# satshakit-mega.net
KiCad netlist of a schematic drawn in EAGLE
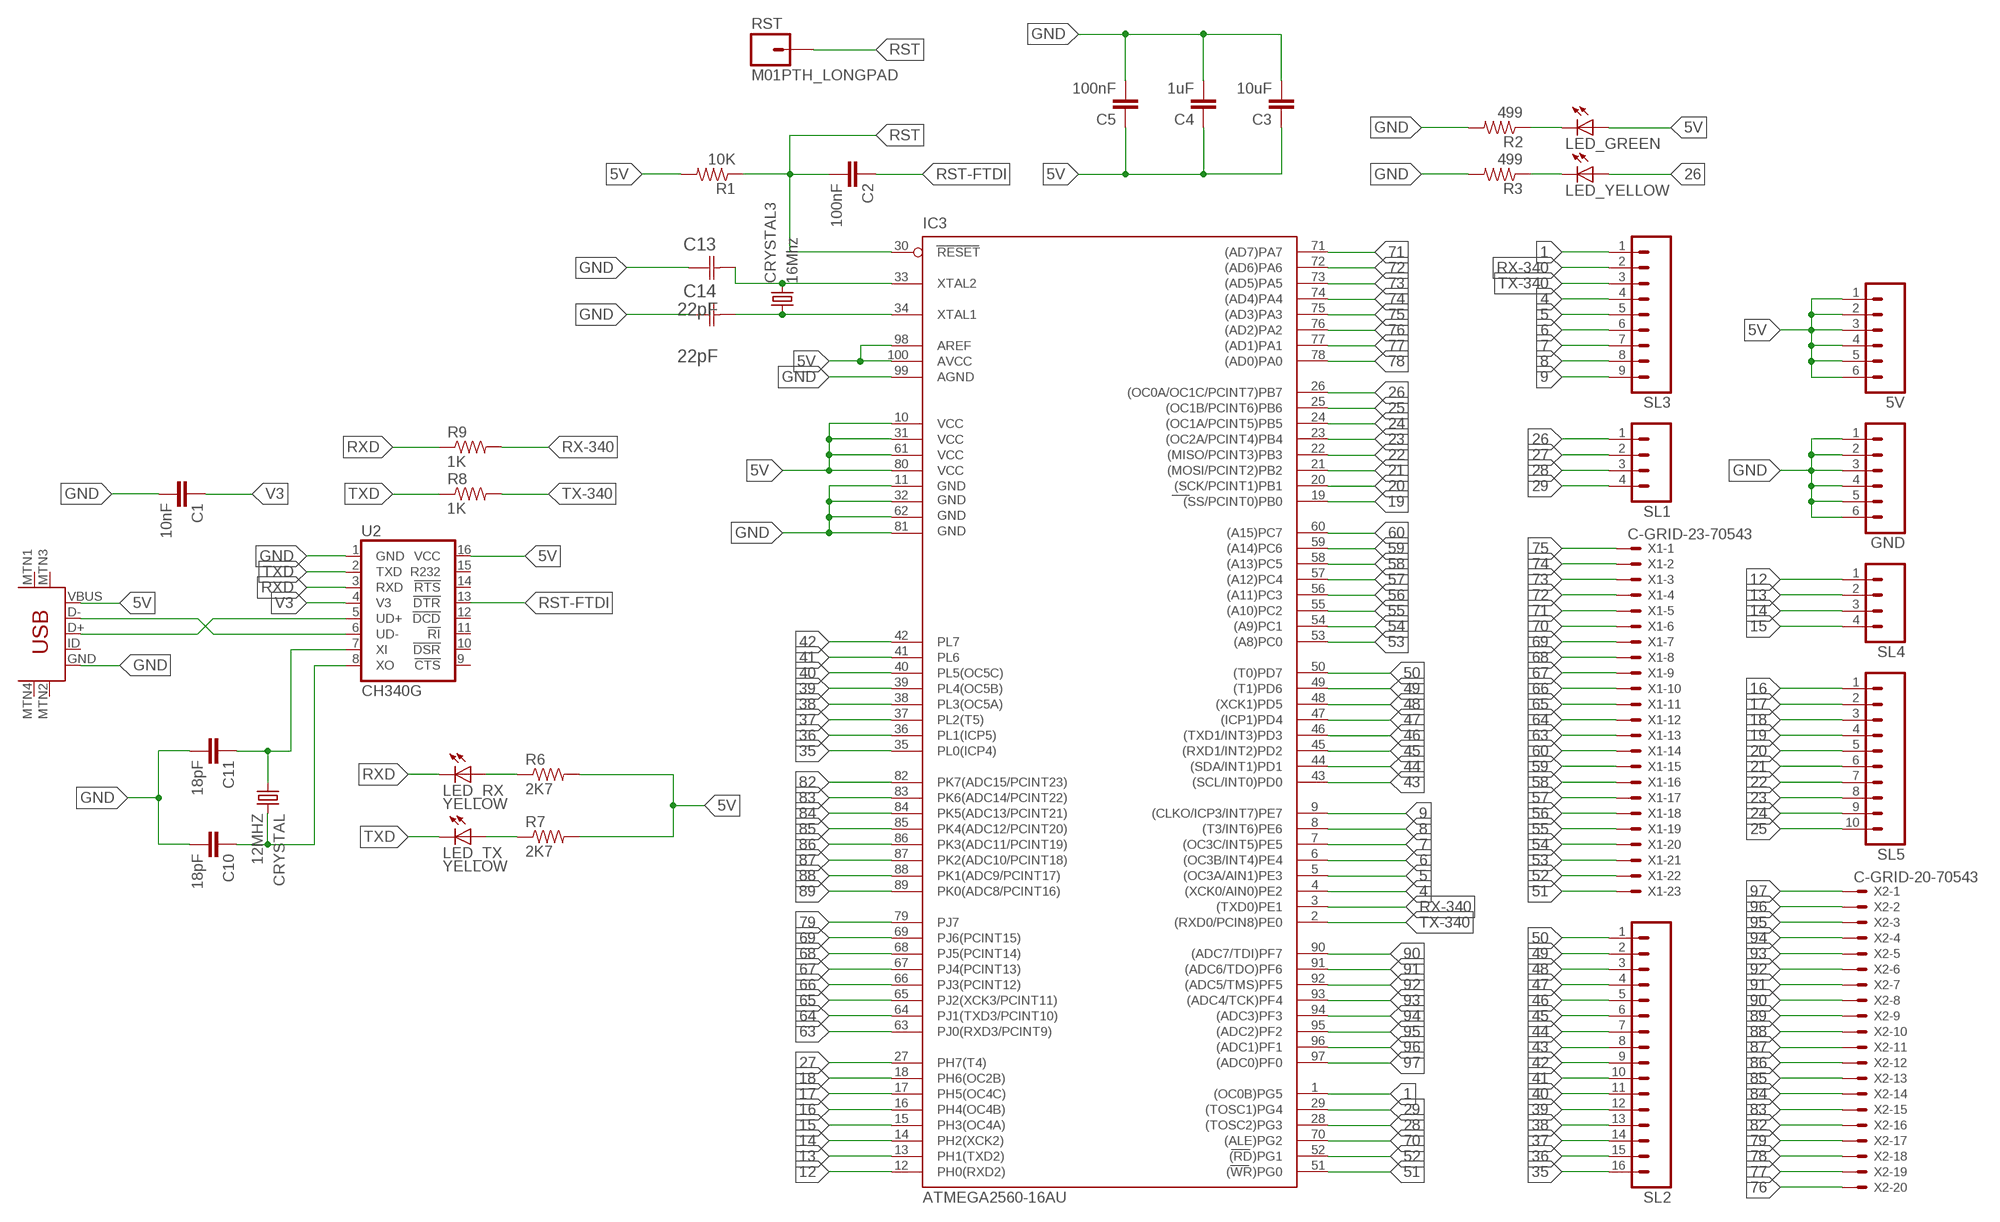
[diagram p0: schematic, sheet 1]

(export (version "E")
  (design (tool "Eeschema 10.0.6"))
  (components
    (comp (ref "5V")
      (value "M06")
      (footprint "eagle-import:06P")
      (libsource (lib "eagle-import") (part "M06"))
    )
    (comp (ref "C1")
      (value "10nF")
      (footprint "eagle-import:1206")
      (libsource (lib "eagle-import") (part "CAP1206"))
    )
    (comp (ref "C2")
      (value "100nF")
      (footprint "eagle-import:1206")
      (libsource (lib "eagle-import") (part "CAP1206"))
    )
    (comp (ref "C3")
      (value "10uF")
      (footprint "eagle-import:1206")
      (libsource (lib "eagle-import") (part "CAP1206"))
    )
    (comp (ref "C4")
      (value "1uF")
      (footprint "eagle-import:1206")
      (libsource (lib "eagle-import") (part "CAP1206"))
    )
    (comp (ref "C5")
      (value "100nF")
      (footprint "eagle-import:1206")
      (libsource (lib "eagle-import") (part "CAP1206"))
    )
    (comp (ref "C10")
      (value "18pF")
      (footprint "eagle-import:1206")
      (libsource (lib "eagle-import") (part "CAP1206"))
    )
    (comp (ref "C11")
      (value "18pF")
      (footprint "eagle-import:1206")
      (libsource (lib "eagle-import") (part "CAP1206"))
    )
    (comp (ref "C13")
      (value "22pF")
      (footprint "eagle-import:CAPC3216X178N")
      (fields (field (name "MPN") "0612ZC225MAT2A") (field (name "TOLERANCE") "±20%"))
      (libsource (lib "eagle-import") (part "0612ZC225MAT2A"))
    )
    (comp (ref "C14")
      (value "22pF")
      (footprint "eagle-import:CAPC3216X178N")
      (fields (field (name "MPN") "0612ZC225MAT2A") (field (name "TOLERANCE") "±20%"))
      (libsource (lib "eagle-import") (part "0612ZC225MAT2A"))
    )
    (comp (ref "CRYSTAL")
      (value "12MHZ")
      (footprint "eagle-import:CSM-7X-DU")
      (libsource (lib "eagle-import") (part "flight_controller.lbr01_FAB_Hello_CSM-7X-DU"))
    )
    (comp (ref "CRYSTAL3")
      (value "16Mhz")
      (footprint "eagle-import:CSM-7X-DU")
      (libsource (lib "eagle-import") (part "CSM-7X-DU"))
    )
    (comp (ref "GND")
      (value "M06")
      (footprint "eagle-import:06P")
      (libsource (lib "eagle-import") (part "M06"))
    )
    (comp (ref "IC3")
      (value "ATMEGA2560-16AU")
      (footprint "eagle-import:TQFP100")
      (libsource (lib "eagle-import") (part "ATMEGAAU1280-16"))
    )
    (comp (ref "LED_GREEN")
      (value "LED1206")
      (footprint "eagle-import:1206")
      (libsource (lib "eagle-import") (part "LED1206"))
    )
    (comp (ref "LED_RX")
      (value "YELLOW")
      (footprint "eagle-import:LED1206")
      (libsource (lib "eagle-import") (part "LED"))
    )
    (comp (ref "LED_TX")
      (value "YELLOW")
      (footprint "eagle-import:LED1206")
      (libsource (lib "eagle-import") (part "LED"))
    )
    (comp (ref "LED_YELLOW")
      (value "LED1206")
      (footprint "eagle-import:1206")
      (libsource (lib "eagle-import") (part "LED1206"))
    )
    (comp (ref "R1")
      (value "10K")
      (footprint "eagle-import:R1206")
      (libsource (lib "eagle-import") (part "RES-US1206"))
    )
    (comp (ref "R2")
      (value "499")
      (footprint "eagle-import:1206")
      (libsource (lib "eagle-import") (part "RESISTOR1206"))
    )
    (comp (ref "R3")
      (value "499")
      (footprint "eagle-import:1206")
      (libsource (lib "eagle-import") (part "RESISTOR1206"))
    )
    (comp (ref "R6")
      (value "2K7")
      (footprint "eagle-import:R1206")
      (libsource (lib "eagle-import") (part "RES-US1206"))
    )
    (comp (ref "R7")
      (value "2K7")
      (footprint "eagle-import:R1206")
      (libsource (lib "eagle-import") (part "RES-US1206"))
    )
    (comp (ref "R8")
      (value "1K")
      (footprint "eagle-import:R1206")
      (libsource (lib "eagle-import") (part "RES-US1206"))
    )
    (comp (ref "R9")
      (value "1K")
      (footprint "eagle-import:R1206")
      (libsource (lib "eagle-import") (part "RES-US1206"))
    )
    (comp (ref "RST")
      (value "M01PTH_LONGPAD")
      (footprint "eagle-import:1X01_LONGPAD")
      (libsource (lib "eagle-import") (part "M01PTH_LONGPAD"))
    )
    (comp (ref "SL1")
      (value "M04")
      (footprint "eagle-import:04P")
      (libsource (lib "eagle-import") (part "M04"))
    )
    (comp (ref "SL2")
      (value "M16")
      (footprint "eagle-import:16P")
      (libsource (lib "eagle-import") (part "M16"))
    )
    (comp (ref "SL3")
      (value "M09")
      (footprint "eagle-import:09P")
      (libsource (lib "eagle-import") (part "M09"))
    )
    (comp (ref "SL4")
      (value "M04")
      (footprint "eagle-import:04P")
      (libsource (lib "eagle-import") (part "M04"))
    )
    (comp (ref "SL5")
      (value "M10")
      (footprint "eagle-import:10P")
      (libsource (lib "eagle-import") (part "M10"))
    )
    (comp (ref "U$7")
      (value "USB-MINIB-5PIN")
      (footprint "eagle-import:USB-MINIB")
      (libsource (lib "eagle-import") (part "USB-MINIB-5PIN"))
    )
    (comp (ref "U2")
      (value "CH340G")
      (footprint "eagle-import:SO016")
      (libsource (lib "eagle-import") (part "CH340GSMD"))
    )
    (comp (ref "X1")
      (value "C-GRID-23-70543")
      (footprint "eagle-import:70543-23")
      (libsource (lib "eagle-import") (part "C-GRID-23-70543"))
    )
    (comp (ref "X2")
      (value "C-GRID-20-70543")
      (footprint "eagle-import:70543-20")
      (libsource (lib "eagle-import") (part "C-GRID-20-70543"))
    )
  )
  (nets
    (net (code "1") (name "1") (class "Default")
      (node (ref "IC3") (pin "1") (pinfunction "(OC0B)PG5_1") (pintype "bidirectional"))
      (node (ref "SL3") (pin "1") (pinfunction "1_1") (pintype "passive"))
    )
    (net (code "2") (name "4") (class "Default")
      (node (ref "IC3") (pin "4") (pinfunction "(XCK0/AIN0)PE2_4") (pintype "bidirectional"))
      (node (ref "SL3") (pin "4") (pinfunction "4_4") (pintype "passive"))
    )
    (net (code "3") (name "5") (class "Default")
      (node (ref "IC3") (pin "5") (pinfunction "(OC3A/AIN1)PE3_5") (pintype "bidirectional"))
      (node (ref "SL3") (pin "5") (pinfunction "5_5") (pintype "passive"))
    )
    (net (code "4") (name "5V") (class "Default")
      (node (ref "5V") (pin "1") (pinfunction "1_1") (pintype "passive"))
      (node (ref "5V") (pin "2") (pinfunction "2_2") (pintype "passive"))
      (node (ref "5V") (pin "3") (pinfunction "3_3") (pintype "passive"))
      (node (ref "5V") (pin "4") (pinfunction "4_4") (pintype "passive"))
      (node (ref "5V") (pin "5") (pinfunction "5_5") (pintype "passive"))
      (node (ref "5V") (pin "6") (pinfunction "6_6") (pintype "passive"))
      (node (ref "C3") (pin "1") (pinfunction "1_1") (pintype "passive"))
      (node (ref "C4") (pin "1") (pinfunction "1_1") (pintype "passive"))
      (node (ref "C5") (pin "1") (pinfunction "1_1") (pintype "passive"))
      (node (ref "IC3") (pin "10") (pinfunction "VCC_10") (pintype "power_in"))
      (node (ref "IC3") (pin "100") (pinfunction "AVCC_100") (pintype "power_in"))
      (node (ref "IC3") (pin "31") (pinfunction "VCC1_31") (pintype "power_in"))
      (node (ref "IC3") (pin "61") (pinfunction "VCC2_61") (pintype "power_in"))
      (node (ref "IC3") (pin "80") (pinfunction "VCC3_80") (pintype "power_in"))
      (node (ref "IC3") (pin "98") (pinfunction "AREF_98") (pintype "bidirectional"))
      (node (ref "LED_GREEN") (pin "1") (pinfunction "A_1") (pintype "passive"))
      (node (ref "R1") (pin "2") (pinfunction "2_2") (pintype "passive"))
      (node (ref "R6") (pin "2") (pinfunction "2_2") (pintype "passive"))
      (node (ref "R7") (pin "2") (pinfunction "2_2") (pintype "passive"))
      (node (ref "U$7") (pin "VBUS") (pinfunction "VBUS_VBUS") (pintype "bidirectional"))
      (node (ref "U2") (pin "16") (pinfunction "VCC_16") (pintype "bidirectional"))
    )
    (net (code "5") (name "6") (class "Default")
      (node (ref "IC3") (pin "6") (pinfunction "(OC3B/INT4)PE4_6") (pintype "bidirectional"))
      (node (ref "SL3") (pin "6") (pinfunction "6_6") (pintype "passive"))
    )
    (net (code "6") (name "7") (class "Default")
      (node (ref "IC3") (pin "7") (pinfunction "(OC3C/INT5)PE5_7") (pintype "bidirectional"))
      (node (ref "SL3") (pin "7") (pinfunction "7_7") (pintype "passive"))
    )
    (net (code "7") (name "8") (class "Default")
      (node (ref "IC3") (pin "8") (pinfunction "(T3/INT6)PE6_8") (pintype "bidirectional"))
      (node (ref "SL3") (pin "8") (pinfunction "8_8") (pintype "passive"))
    )
    (net (code "8") (name "9") (class "Default")
      (node (ref "IC3") (pin "9") (pinfunction "(CLKO/ICP3/INT7)PE7_9") (pintype "bidirectional"))
      (node (ref "SL3") (pin "9") (pinfunction "9_9") (pintype "passive"))
    )
    (net (code "9") (name "12") (class "Default")
      (node (ref "IC3") (pin "12") (pinfunction "PH0(RXD2)_12") (pintype "bidirectional"))
      (node (ref "SL4") (pin "1") (pinfunction "1_1") (pintype "passive"))
    )
    (net (code "10") (name "13") (class "Default")
      (node (ref "IC3") (pin "13") (pinfunction "PH1(TXD2)_13") (pintype "bidirectional"))
      (node (ref "SL4") (pin "2") (pinfunction "2_2") (pintype "passive"))
    )
    (net (code "11") (name "14") (class "Default")
      (node (ref "IC3") (pin "14") (pinfunction "PH2(XCK2)_14") (pintype "bidirectional"))
      (node (ref "SL4") (pin "3") (pinfunction "3_3") (pintype "passive"))
    )
    (net (code "12") (name "15") (class "Default")
      (node (ref "IC3") (pin "15") (pinfunction "PH3(OC4A)_15") (pintype "bidirectional"))
      (node (ref "SL4") (pin "4") (pinfunction "4_4") (pintype "passive"))
    )
    (net (code "13") (name "16") (class "Default")
      (node (ref "IC3") (pin "16") (pinfunction "PH4(OC4B)_16") (pintype "bidirectional"))
      (node (ref "SL5") (pin "1") (pinfunction "1_1") (pintype "passive"))
    )
    (net (code "14") (name "17") (class "Default")
      (node (ref "IC3") (pin "17") (pinfunction "PH5(OC4C)_17") (pintype "bidirectional"))
      (node (ref "SL5") (pin "2") (pinfunction "2_2") (pintype "passive"))
    )
    (net (code "15") (name "18") (class "Default")
      (node (ref "IC3") (pin "18") (pinfunction "PH6(OC2B)_18") (pintype "bidirectional"))
      (node (ref "SL5") (pin "3") (pinfunction "3_3") (pintype "passive"))
    )
    (net (code "16") (name "19") (class "Default")
      (node (ref "IC3") (pin "19") (pinfunction "(SS/PCINT0)PB0_19") (pintype "bidirectional"))
      (node (ref "SL5") (pin "4") (pinfunction "4_4") (pintype "passive"))
    )
    (net (code "17") (name "20") (class "Default")
      (node (ref "IC3") (pin "20") (pinfunction "(SCK/PCINT1)PB1_20") (pintype "bidirectional"))
      (node (ref "SL5") (pin "5") (pinfunction "5_5") (pintype "passive"))
    )
    (net (code "18") (name "21") (class "Default")
      (node (ref "IC3") (pin "21") (pinfunction "(MOSI/PCINT2)PB2_21") (pintype "bidirectional"))
      (node (ref "SL5") (pin "6") (pinfunction "6_6") (pintype "passive"))
    )
    (net (code "19") (name "22") (class "Default")
      (node (ref "IC3") (pin "22") (pinfunction "(MISO/PCINT3)PB3_22") (pintype "bidirectional"))
      (node (ref "SL5") (pin "7") (pinfunction "7_7") (pintype "passive"))
    )
    (net (code "20") (name "23") (class "Default")
      (node (ref "IC3") (pin "23") (pinfunction "(OC2A/PCINT4)PB4_23") (pintype "bidirectional"))
      (node (ref "SL5") (pin "8") (pinfunction "8_8") (pintype "passive"))
    )
    (net (code "21") (name "24") (class "Default")
      (node (ref "IC3") (pin "24") (pinfunction "(OC1A/PCINT5)PB5_24") (pintype "bidirectional"))
      (node (ref "SL5") (pin "9") (pinfunction "9_9") (pintype "passive"))
    )
    (net (code "22") (name "25") (class "Default")
      (node (ref "IC3") (pin "25") (pinfunction "(OC1B/PCINT6)PB6_25") (pintype "bidirectional"))
      (node (ref "SL5") (pin "10") (pinfunction "10_10") (pintype "passive"))
    )
    (net (code "23") (name "26") (class "Default")
      (node (ref "IC3") (pin "26") (pinfunction "(OC0A/OC1C/PCINT7)PB7_26") (pintype "bidirectional"))
      (node (ref "LED_YELLOW") (pin "1") (pinfunction "A_1") (pintype "passive"))
      (node (ref "SL1") (pin "1") (pinfunction "1_1") (pintype "passive"))
    )
    (net (code "24") (name "27") (class "Default")
      (node (ref "IC3") (pin "27") (pinfunction "PH7(T4)_27") (pintype "bidirectional"))
      (node (ref "SL1") (pin "2") (pinfunction "2_2") (pintype "passive"))
    )
    (net (code "25") (name "28") (class "Default")
      (node (ref "IC3") (pin "28") (pinfunction "(TOSC2)PG3_28") (pintype "bidirectional"))
      (node (ref "SL1") (pin "3") (pinfunction "3_3") (pintype "passive"))
    )
    (net (code "26") (name "29") (class "Default")
      (node (ref "IC3") (pin "29") (pinfunction "(TOSC1)PG4_29") (pintype "bidirectional"))
      (node (ref "SL1") (pin "4") (pinfunction "4_4") (pintype "passive"))
    )
    (net (code "27") (name "35") (class "Default")
      (node (ref "IC3") (pin "35") (pinfunction "PL0(ICP4)_35") (pintype "bidirectional"))
      (node (ref "SL2") (pin "16") (pinfunction "16_16") (pintype "passive"))
    )
    (net (code "28") (name "36") (class "Default")
      (node (ref "IC3") (pin "36") (pinfunction "PL1(ICP5)_36") (pintype "bidirectional"))
      (node (ref "SL2") (pin "15") (pinfunction "15_15") (pintype "passive"))
    )
    (net (code "29") (name "37") (class "Default")
      (node (ref "IC3") (pin "37") (pinfunction "PL2(T5)_37") (pintype "bidirectional"))
      (node (ref "SL2") (pin "14") (pinfunction "14_14") (pintype "passive"))
    )
    (net (code "30") (name "38") (class "Default")
      (node (ref "IC3") (pin "38") (pinfunction "PL3(OC5A)_38") (pintype "bidirectional"))
      (node (ref "SL2") (pin "13") (pinfunction "13_13") (pintype "passive"))
    )
    (net (code "31") (name "39") (class "Default")
      (node (ref "IC3") (pin "39") (pinfunction "PL4(OC5B)_39") (pintype "bidirectional"))
      (node (ref "SL2") (pin "12") (pinfunction "12_12") (pintype "passive"))
    )
    (net (code "32") (name "40") (class "Default")
      (node (ref "IC3") (pin "40") (pinfunction "PL5(OC5C)_40") (pintype "bidirectional"))
      (node (ref "SL2") (pin "11") (pinfunction "11_11") (pintype "passive"))
    )
    (net (code "33") (name "41") (class "Default")
      (node (ref "IC3") (pin "41") (pinfunction "PL6_41") (pintype "bidirectional"))
      (node (ref "SL2") (pin "10") (pinfunction "10_10") (pintype "passive"))
    )
    (net (code "34") (name "42") (class "Default")
      (node (ref "IC3") (pin "42") (pinfunction "PL7_42") (pintype "bidirectional"))
      (node (ref "SL2") (pin "9") (pinfunction "9_9") (pintype "passive"))
    )
    (net (code "35") (name "43") (class "Default")
      (node (ref "IC3") (pin "43") (pinfunction "(SCL/INT0)PD0_43") (pintype "bidirectional"))
      (node (ref "SL2") (pin "8") (pinfunction "8_8") (pintype "passive"))
    )
    (net (code "36") (name "44") (class "Default")
      (node (ref "IC3") (pin "44") (pinfunction "(SDA/INT1)PD1_44") (pintype "bidirectional"))
      (node (ref "SL2") (pin "7") (pinfunction "7_7") (pintype "passive"))
    )
    (net (code "37") (name "45") (class "Default")
      (node (ref "IC3") (pin "45") (pinfunction "(RXD1/INT2)PD2_45") (pintype "bidirectional"))
      (node (ref "SL2") (pin "6") (pinfunction "6_6") (pintype "passive"))
    )
    (net (code "38") (name "46") (class "Default")
      (node (ref "IC3") (pin "46") (pinfunction "(TXD1/INT3)PD3_46") (pintype "bidirectional"))
      (node (ref "SL2") (pin "5") (pinfunction "5_5") (pintype "passive"))
    )
    (net (code "39") (name "47") (class "Default")
      (node (ref "IC3") (pin "47") (pinfunction "(ICP1)PD4_47") (pintype "bidirectional"))
      (node (ref "SL2") (pin "4") (pinfunction "4_4") (pintype "passive"))
    )
    (net (code "40") (name "48") (class "Default")
      (node (ref "IC3") (pin "48") (pinfunction "(XCK1)PD5_48") (pintype "bidirectional"))
      (node (ref "SL2") (pin "3") (pinfunction "3_3") (pintype "passive"))
    )
    (net (code "41") (name "49") (class "Default")
      (node (ref "IC3") (pin "49") (pinfunction "(T1)PD6_49") (pintype "bidirectional"))
      (node (ref "SL2") (pin "2") (pinfunction "2_2") (pintype "passive"))
    )
    (net (code "42") (name "50") (class "Default")
      (node (ref "IC3") (pin "50") (pinfunction "(T0)PD7_50") (pintype "bidirectional"))
      (node (ref "SL2") (pin "1") (pinfunction "1_1") (pintype "passive"))
    )
    (net (code "43") (name "51") (class "Default")
      (node (ref "IC3") (pin "51") (pinfunction "(WR)PG0_51") (pintype "bidirectional"))
      (node (ref "X1") (pin "23") (pinfunction "S_23") (pintype "passive"))
    )
    (net (code "44") (name "52") (class "Default")
      (node (ref "IC3") (pin "52") (pinfunction "(RD)PG1_52") (pintype "bidirectional"))
      (node (ref "X1") (pin "22") (pinfunction "S_22") (pintype "passive"))
    )
    (net (code "45") (name "53") (class "Default")
      (node (ref "IC3") (pin "53") (pinfunction "(A8)PC0_53") (pintype "bidirectional"))
      (node (ref "X1") (pin "21") (pinfunction "S_21") (pintype "passive"))
    )
    (net (code "46") (name "54") (class "Default")
      (node (ref "IC3") (pin "54") (pinfunction "(A9)PC1_54") (pintype "bidirectional"))
      (node (ref "X1") (pin "20") (pinfunction "S_20") (pintype "passive"))
    )
    (net (code "47") (name "55") (class "Default")
      (node (ref "IC3") (pin "55") (pinfunction "(A10)PC2_55") (pintype "bidirectional"))
      (node (ref "X1") (pin "19") (pinfunction "S_19") (pintype "passive"))
    )
    (net (code "48") (name "56") (class "Default")
      (node (ref "IC3") (pin "56") (pinfunction "(A11)PC3_56") (pintype "bidirectional"))
      (node (ref "X1") (pin "18") (pinfunction "S_18") (pintype "passive"))
    )
    (net (code "49") (name "57") (class "Default")
      (node (ref "IC3") (pin "57") (pinfunction "(A12)PC4_57") (pintype "bidirectional"))
      (node (ref "X1") (pin "17") (pinfunction "S_17") (pintype "passive"))
    )
    (net (code "50") (name "58") (class "Default")
      (node (ref "IC3") (pin "58") (pinfunction "(A13)PC5_58") (pintype "bidirectional"))
      (node (ref "X1") (pin "16") (pinfunction "S_16") (pintype "passive"))
    )
    (net (code "51") (name "59") (class "Default")
      (node (ref "IC3") (pin "59") (pinfunction "(A14)PC6_59") (pintype "bidirectional"))
      (node (ref "X1") (pin "15") (pinfunction "S_15") (pintype "passive"))
    )
    (net (code "52") (name "60") (class "Default")
      (node (ref "IC3") (pin "60") (pinfunction "(A15)PC7_60") (pintype "bidirectional"))
      (node (ref "X1") (pin "14") (pinfunction "S_14") (pintype "passive"))
    )
    (net (code "53") (name "63") (class "Default")
      (node (ref "IC3") (pin "63") (pinfunction "PJ0(RXD3/PCINT9)_63") (pintype "bidirectional"))
      (node (ref "X1") (pin "13") (pinfunction "S_13") (pintype "passive"))
    )
    (net (code "54") (name "64") (class "Default")
      (node (ref "IC3") (pin "64") (pinfunction "PJ1(TXD3/PCINT10)_64") (pintype "bidirectional"))
      (node (ref "X1") (pin "12") (pinfunction "S_12") (pintype "passive"))
    )
    (net (code "55") (name "65") (class "Default")
      (node (ref "IC3") (pin "65") (pinfunction "PJ2(XCK3/PCINT11)_65") (pintype "bidirectional"))
      (node (ref "X1") (pin "11") (pinfunction "S_11") (pintype "passive"))
    )
    (net (code "56") (name "66") (class "Default")
      (node (ref "IC3") (pin "66") (pinfunction "PJ3(PCINT12)_66") (pintype "bidirectional"))
      (node (ref "X1") (pin "10") (pinfunction "S_10") (pintype "passive"))
    )
    (net (code "57") (name "67") (class "Default")
      (node (ref "IC3") (pin "67") (pinfunction "PJ4(PCINT13)_67") (pintype "bidirectional"))
      (node (ref "X1") (pin "9") (pinfunction "S_9") (pintype "passive"))
    )
    (net (code "58") (name "68") (class "Default")
      (node (ref "IC3") (pin "68") (pinfunction "PJ5(PCINT14)_68") (pintype "bidirectional"))
      (node (ref "X1") (pin "8") (pinfunction "S_8") (pintype "passive"))
    )
    (net (code "59") (name "69") (class "Default")
      (node (ref "IC3") (pin "69") (pinfunction "PJ6(PCINT15)_69") (pintype "bidirectional"))
      (node (ref "X1") (pin "7") (pinfunction "S_7") (pintype "passive"))
    )
    (net (code "60") (name "70") (class "Default")
      (node (ref "IC3") (pin "70") (pinfunction "(ALE)PG2_70") (pintype "bidirectional"))
      (node (ref "X1") (pin "6") (pinfunction "S_6") (pintype "passive"))
    )
    (net (code "61") (name "71") (class "Default")
      (node (ref "IC3") (pin "71") (pinfunction "(AD7)PA7_71") (pintype "bidirectional"))
      (node (ref "X1") (pin "5") (pinfunction "S_5") (pintype "passive"))
    )
    (net (code "62") (name "72") (class "Default")
      (node (ref "IC3") (pin "72") (pinfunction "(AD6)PA6_72") (pintype "bidirectional"))
      (node (ref "X1") (pin "4") (pinfunction "S_4") (pintype "passive"))
    )
    (net (code "63") (name "73") (class "Default")
      (node (ref "IC3") (pin "73") (pinfunction "(AD5)PA5_73") (pintype "bidirectional"))
      (node (ref "X1") (pin "3") (pinfunction "S_3") (pintype "passive"))
    )
    (net (code "64") (name "74") (class "Default")
      (node (ref "IC3") (pin "74") (pinfunction "(AD4)PA4_74") (pintype "bidirectional"))
      (node (ref "X1") (pin "2") (pinfunction "S_2") (pintype "passive"))
    )
    (net (code "65") (name "75") (class "Default")
      (node (ref "IC3") (pin "75") (pinfunction "(AD3)PA3_75") (pintype "bidirectional"))
      (node (ref "X1") (pin "1") (pinfunction "S_1") (pintype "passive"))
    )
    (net (code "66") (name "76") (class "Default")
      (node (ref "IC3") (pin "76") (pinfunction "(AD2)PA2_76") (pintype "bidirectional"))
      (node (ref "X2") (pin "20") (pinfunction "S_20") (pintype "passive"))
    )
    (net (code "67") (name "77") (class "Default")
      (node (ref "IC3") (pin "77") (pinfunction "(AD1)PA1_77") (pintype "bidirectional"))
      (node (ref "X2") (pin "19") (pinfunction "S_19") (pintype "passive"))
    )
    (net (code "68") (name "78") (class "Default")
      (node (ref "IC3") (pin "78") (pinfunction "(AD0)PA0_78") (pintype "bidirectional"))
      (node (ref "X2") (pin "18") (pinfunction "S_18") (pintype "passive"))
    )
    (net (code "69") (name "79") (class "Default")
      (node (ref "IC3") (pin "79") (pinfunction "PJ7_79") (pintype "bidirectional"))
      (node (ref "X2") (pin "17") (pinfunction "S_17") (pintype "passive"))
    )
    (net (code "70") (name "82") (class "Default")
      (node (ref "IC3") (pin "82") (pinfunction "PK7(ADC15/PCINT23)_82") (pintype "bidirectional"))
      (node (ref "X2") (pin "16") (pinfunction "S_16") (pintype "passive"))
    )
    (net (code "71") (name "83") (class "Default")
      (node (ref "IC3") (pin "83") (pinfunction "PK6(ADC14/PCINT22)_83") (pintype "bidirectional"))
      (node (ref "X2") (pin "15") (pinfunction "S_15") (pintype "passive"))
    )
    (net (code "72") (name "84") (class "Default")
      (node (ref "IC3") (pin "84") (pinfunction "PK5(ADC13/PCINT21)_84") (pintype "bidirectional"))
      (node (ref "X2") (pin "14") (pinfunction "S_14") (pintype "passive"))
    )
    (net (code "73") (name "85") (class "Default")
      (node (ref "IC3") (pin "85") (pinfunction "PK4(ADC12/PCINT20)_85") (pintype "bidirectional"))
      (node (ref "X2") (pin "13") (pinfunction "S_13") (pintype "passive"))
    )
    (net (code "74") (name "86") (class "Default")
      (node (ref "IC3") (pin "86") (pinfunction "PK3(ADC11/PCINT19)_86") (pintype "bidirectional"))
      (node (ref "X2") (pin "12") (pinfunction "S_12") (pintype "passive"))
    )
    (net (code "75") (name "87") (class "Default")
      (node (ref "IC3") (pin "87") (pinfunction "PK2(ADC10/PCINT18)_87") (pintype "bidirectional"))
      (node (ref "X2") (pin "11") (pinfunction "S_11") (pintype "passive"))
    )
    (net (code "76") (name "88") (class "Default")
      (node (ref "IC3") (pin "88") (pinfunction "PK1(ADC9/PCINT17)_88") (pintype "bidirectional"))
      (node (ref "X2") (pin "10") (pinfunction "S_10") (pintype "passive"))
    )
    (net (code "77") (name "89") (class "Default")
      (node (ref "IC3") (pin "89") (pinfunction "PK0(ADC8/PCINT16)_89") (pintype "bidirectional"))
      (node (ref "X2") (pin "9") (pinfunction "S_9") (pintype "passive"))
    )
    (net (code "78") (name "90") (class "Default")
      (node (ref "IC3") (pin "90") (pinfunction "(ADC7/TDI)PF7_90") (pintype "bidirectional"))
      (node (ref "X2") (pin "8") (pinfunction "S_8") (pintype "passive"))
    )
    (net (code "79") (name "91") (class "Default")
      (node (ref "IC3") (pin "91") (pinfunction "(ADC6/TDO)PF6_91") (pintype "bidirectional"))
      (node (ref "X2") (pin "7") (pinfunction "S_7") (pintype "passive"))
    )
    (net (code "80") (name "92") (class "Default")
      (node (ref "IC3") (pin "92") (pinfunction "(ADC5/TMS)PF5_92") (pintype "bidirectional"))
      (node (ref "X2") (pin "6") (pinfunction "S_6") (pintype "passive"))
    )
    (net (code "81") (name "93") (class "Default")
      (node (ref "IC3") (pin "93") (pinfunction "(ADC4/TCK)PF4_93") (pintype "bidirectional"))
      (node (ref "X2") (pin "5") (pinfunction "S_5") (pintype "passive"))
    )
    (net (code "82") (name "94") (class "Default")
      (node (ref "IC3") (pin "94") (pinfunction "(ADC3)PF3_94") (pintype "bidirectional"))
      (node (ref "X2") (pin "4") (pinfunction "S_4") (pintype "passive"))
    )
    (net (code "83") (name "95") (class "Default")
      (node (ref "IC3") (pin "95") (pinfunction "(ADC2)PF2_95") (pintype "bidirectional"))
      (node (ref "X2") (pin "3") (pinfunction "S_3") (pintype "passive"))
    )
    (net (code "84") (name "96") (class "Default")
      (node (ref "IC3") (pin "96") (pinfunction "(ADC1)PF1_96") (pintype "bidirectional"))
      (node (ref "X2") (pin "2") (pinfunction "S_2") (pintype "passive"))
    )
    (net (code "85") (name "97") (class "Default")
      (node (ref "IC3") (pin "97") (pinfunction "(ADC0)PF0_97") (pintype "bidirectional"))
      (node (ref "X2") (pin "1") (pinfunction "S_1") (pintype "passive"))
    )
    (net (code "86") (name "GND") (class "Default")
      (node (ref "C1") (pin "2") (pinfunction "2_2") (pintype "passive"))
      (node (ref "C10") (pin "2") (pinfunction "2_2") (pintype "passive"))
      (node (ref "C11") (pin "2") (pinfunction "2_2") (pintype "passive"))
      (node (ref "C13") (pin "1") (pinfunction "C1_1") (pintype "passive"))
      (node (ref "C14") (pin "1") (pinfunction "C1_1") (pintype "passive"))
      (node (ref "C3") (pin "2") (pinfunction "2_2") (pintype "passive"))
      (node (ref "C4") (pin "2") (pinfunction "2_2") (pintype "passive"))
      (node (ref "C5") (pin "2") (pinfunction "2_2") (pintype "passive"))
      (node (ref "GND") (pin "1") (pinfunction "1_1") (pintype "passive"))
      (node (ref "GND") (pin "2") (pinfunction "2_2") (pintype "passive"))
      (node (ref "GND") (pin "3") (pinfunction "3_3") (pintype "passive"))
      (node (ref "GND") (pin "4") (pinfunction "4_4") (pintype "passive"))
      (node (ref "GND") (pin "5") (pinfunction "5_5") (pintype "passive"))
      (node (ref "GND") (pin "6") (pinfunction "6_6") (pintype "passive"))
      (node (ref "IC3") (pin "11") (pinfunction "GND_11") (pintype "power_in"))
      (node (ref "IC3") (pin "32") (pinfunction "GND1_32") (pintype "power_in"))
      (node (ref "IC3") (pin "62") (pinfunction "GND2_62") (pintype "power_in"))
      (node (ref "IC3") (pin "81") (pinfunction "GND3_81") (pintype "power_in"))
      (node (ref "IC3") (pin "99") (pinfunction "AGND_99") (pintype "power_in"))
      (node (ref "R2") (pin "2") (pinfunction "2_2") (pintype "passive"))
      (node (ref "R3") (pin "2") (pinfunction "2_2") (pintype "passive"))
      (node (ref "U$7") (pin "GND") (pinfunction "GND_GND") (pintype "bidirectional"))
      (node (ref "U2") (pin "1") (pinfunction "GND_1") (pintype "bidirectional"))
    )
    (net (code "87") (name "Net-(C13-C2)") (class "Default")
      (node (ref "C13") (pin "2") (pinfunction "C2_2") (pintype "passive"))
      (node (ref "CRYSTAL3") (pin "2") (pinfunction "2_2") (pintype "passive"))
      (node (ref "IC3") (pin "33") (pinfunction "XTAL2_33") (pintype "output"))
    )
    (net (code "88") (name "Net-(C14-C2)") (class "Default")
      (node (ref "C14") (pin "2") (pinfunction "C2_2") (pintype "passive"))
      (node (ref "CRYSTAL3") (pin "1") (pinfunction "1_1") (pintype "passive"))
      (node (ref "IC3") (pin "34") (pinfunction "XTAL1_34") (pintype "input"))
    )
    (net (code "89") (name "Net-(LED_GREEN-C)") (class "Default")
      (node (ref "LED_GREEN") (pin "2") (pinfunction "C_2") (pintype "passive"))
      (node (ref "R2") (pin "1") (pinfunction "1_1") (pintype "passive"))
    )
    (net (code "90") (name "Net-(LED_RX-A)") (class "Default")
      (node (ref "LED_RX") (pin "1") (pinfunction "A_1") (pintype "passive"))
      (node (ref "R6") (pin "1") (pinfunction "1_1") (pintype "passive"))
    )
    (net (code "91") (name "Net-(LED_TX-A)") (class "Default")
      (node (ref "LED_TX") (pin "1") (pinfunction "A_1") (pintype "passive"))
      (node (ref "R7") (pin "1") (pinfunction "1_1") (pintype "passive"))
    )
    (net (code "92") (name "Net-(LED_YELLOW-C)") (class "Default")
      (node (ref "LED_YELLOW") (pin "2") (pinfunction "C_2") (pintype "passive"))
      (node (ref "R3") (pin "1") (pinfunction "1_1") (pintype "passive"))
    )
    (net (code "93") (name "Net-(U2-UD+)") (class "Default")
      (node (ref "U$7") (pin "D+") (pinfunction "D+_D+") (pintype "bidirectional"))
      (node (ref "U2") (pin "5") (pinfunction "UD+_5") (pintype "bidirectional"))
    )
    (net (code "94") (name "Net-(U2-UD-)") (class "Default")
      (node (ref "U$7") (pin "D-") (pinfunction "D-_D-") (pintype "bidirectional"))
      (node (ref "U2") (pin "6") (pinfunction "UD-_6") (pintype "bidirectional"))
    )
    (net (code "95") (name "Net-(U2-XI)") (class "Default")
      (node (ref "C11") (pin "1") (pinfunction "1_1") (pintype "passive"))
      (node (ref "CRYSTAL") (pin "1") (pinfunction "1_1") (pintype "passive"))
      (node (ref "U2") (pin "7") (pinfunction "XI_7") (pintype "bidirectional"))
    )
    (net (code "96") (name "Net-(U2-XO)") (class "Default")
      (node (ref "C10") (pin "1") (pinfunction "1_1") (pintype "passive"))
      (node (ref "CRYSTAL") (pin "2") (pinfunction "2_2") (pintype "passive"))
      (node (ref "U2") (pin "8") (pinfunction "XO_8") (pintype "bidirectional"))
    )
    (net (code "97") (name "RST") (class "Default")
      (node (ref "C2") (pin "2") (pinfunction "2_2") (pintype "passive"))
      (node (ref "IC3") (pin "30") (pinfunction "RESET_30") (pintype "input"))
      (node (ref "R1") (pin "1") (pinfunction "1_1") (pintype "passive"))
      (node (ref "RST") (pin "1") (pinfunction "1_1") (pintype "passive"))
    )
    (net (code "98") (name "RST-FTDI") (class "Default")
      (node (ref "C2") (pin "1") (pinfunction "1_1") (pintype "passive"))
      (node (ref "U2") (pin "13") (pinfunction "~{DTR}_13") (pintype "bidirectional"))
    )
    (net (code "99") (name "RX-340") (class "Default")
      (node (ref "IC3") (pin "3") (pinfunction "(TXD0)PE1_3") (pintype "bidirectional"))
      (node (ref "R9") (pin "2") (pinfunction "2_2") (pintype "passive"))
      (node (ref "SL3") (pin "2") (pinfunction "2_2") (pintype "passive"))
    )
    (net (code "100") (name "RXD") (class "Default")
      (node (ref "LED_RX") (pin "2") (pinfunction "C_2") (pintype "passive"))
      (node (ref "R9") (pin "1") (pinfunction "1_1") (pintype "passive"))
      (node (ref "U2") (pin "3") (pinfunction "RXD_3") (pintype "bidirectional"))
    )
    (net (code "101") (name "TX-340") (class "Default")
      (node (ref "IC3") (pin "2") (pinfunction "(RXD0/PCIN8)PE0_2") (pintype "bidirectional"))
      (node (ref "R8") (pin "2") (pinfunction "2_2") (pintype "passive"))
      (node (ref "SL3") (pin "3") (pinfunction "3_3") (pintype "passive"))
    )
    (net (code "102") (name "TXD") (class "Default")
      (node (ref "LED_TX") (pin "2") (pinfunction "C_2") (pintype "passive"))
      (node (ref "R8") (pin "1") (pinfunction "1_1") (pintype "passive"))
      (node (ref "U2") (pin "2") (pinfunction "TXD_2") (pintype "bidirectional"))
    )
    (net (code "103") (name "V3") (class "Default")
      (node (ref "C1") (pin "1") (pinfunction "1_1") (pintype "passive"))
      (node (ref "U2") (pin "4") (pinfunction "V3_4") (pintype "bidirectional"))
    )
    (net (code "104") (name "unconnected-(U$7-MTN1-PadMTN3)") (class "Default")
      (node (ref "U$7") (pin "MTN3") (pinfunction "MTN1_MTN3") (pintype "bidirectional"))
    )
    (net (code "105") (name "unconnected-(U$7-MTN2-PadMTN1)") (class "Default")
      (node (ref "U$7") (pin "MTN1") (pinfunction "MTN2_MTN1") (pintype "bidirectional"))
    )
    (net (code "106") (name "unconnected-(U$7-MTN3-PadMTN2)") (class "Default")
      (node (ref "U$7") (pin "MTN2") (pinfunction "MTN3_MTN2") (pintype "bidirectional"))
    )
    (net (code "107") (name "unconnected-(U$7-PadID)") (class "Default")
      (node (ref "U$7") (pin "ID") (pinfunction "ID_ID") (pintype "bidirectional"))
    )
    (net (code "108") (name "unconnected-(U$7-PadMTN4)") (class "Default")
      (node (ref "U$7") (pin "MTN4") (pinfunction "MTN4_MTN4") (pintype "bidirectional"))
    )
    (net (code "109") (name "unconnected-(U2-R232-Pad15)") (class "Default")
      (node (ref "U2") (pin "15") (pinfunction "R232_15") (pintype "bidirectional"))
    )
    (net (code "110") (name "unconnected-(U2-~{CTS}-Pad9)") (class "Default")
      (node (ref "U2") (pin "9") (pinfunction "~{CTS}_9") (pintype "bidirectional"))
    )
    (net (code "111") (name "unconnected-(U2-~{DCD}-Pad12)") (class "Default")
      (node (ref "U2") (pin "12") (pinfunction "~{DCD}_12") (pintype "bidirectional"))
    )
    (net (code "112") (name "unconnected-(U2-~{DSR}-Pad10)") (class "Default")
      (node (ref "U2") (pin "10") (pinfunction "~{DSR}_10") (pintype "bidirectional"))
    )
    (net (code "113") (name "unconnected-(U2-~{RI}-Pad11)") (class "Default")
      (node (ref "U2") (pin "11") (pinfunction "~{RI}_11") (pintype "bidirectional"))
    )
    (net (code "114") (name "unconnected-(U2-~{RTS}-Pad14)") (class "Default")
      (node (ref "U2") (pin "14") (pinfunction "~{RTS}_14") (pintype "bidirectional"))
    )
  )
)
